# USB_Circuitry.net
KiCad netlist of a schematic drawn in Altium Designer
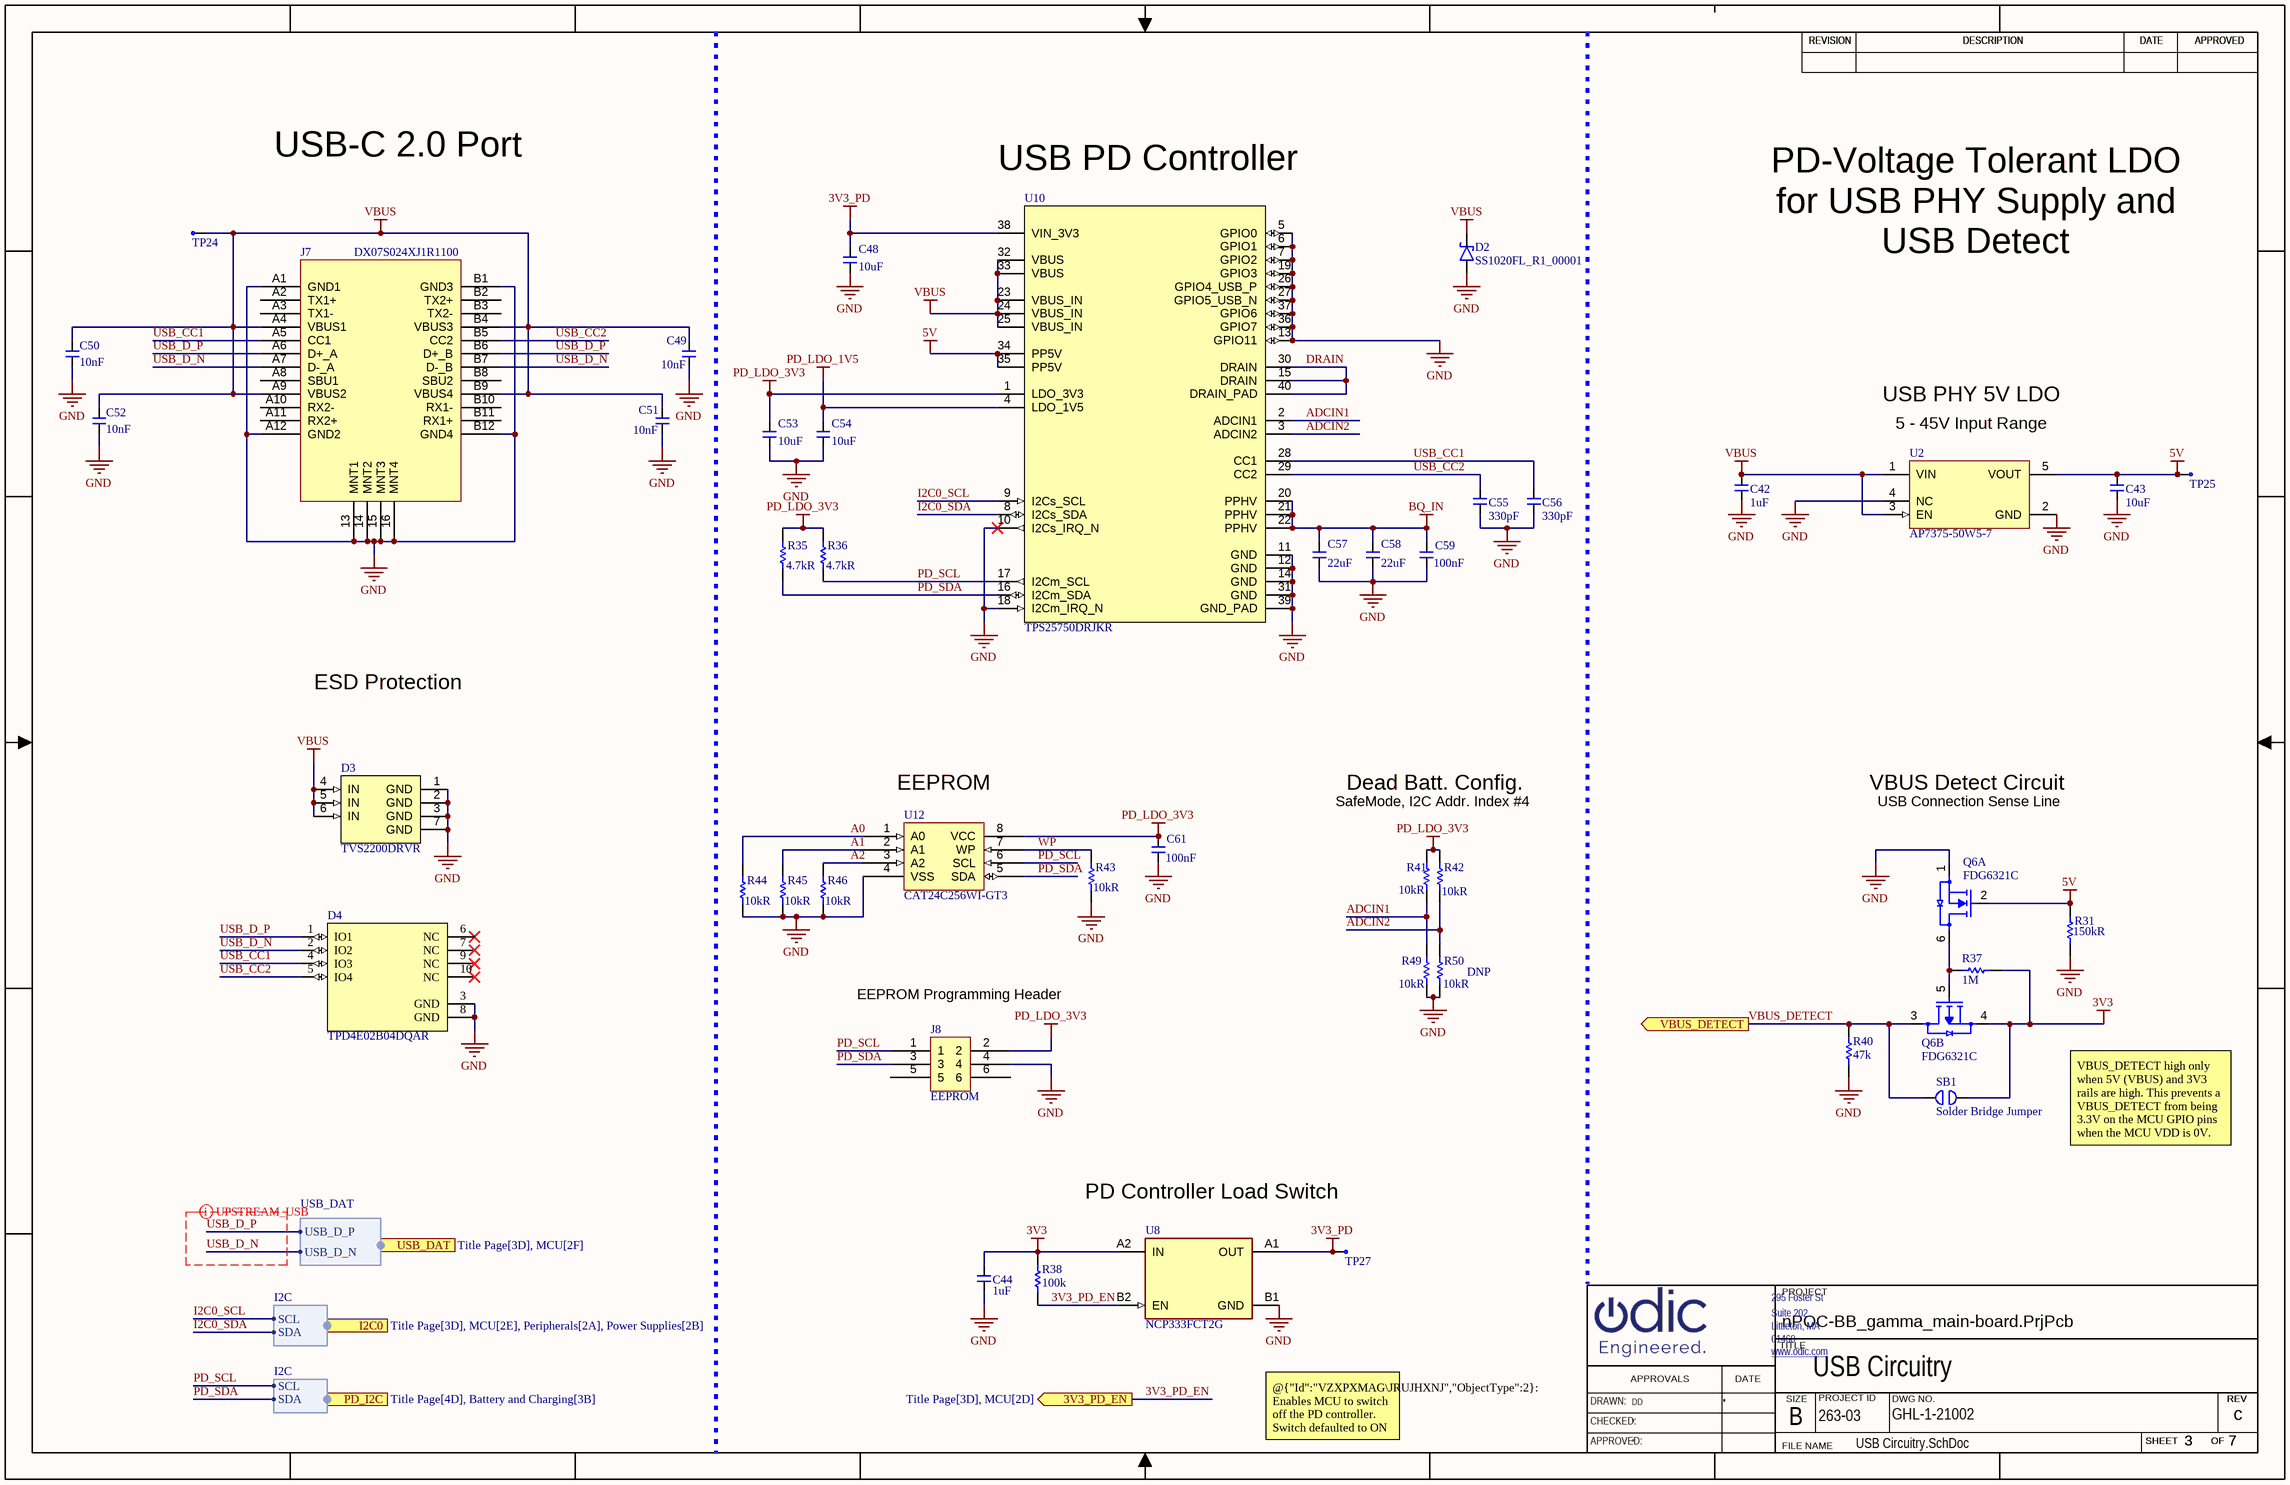
[diagram p0: USB Circuitry.SchDoc]

(export (version "E")
  (design (tool "Eeschema 10.0.6"))
  (components
    (comp (ref "C42")
      (value "1uF")
      (footprint "C0603")
      (description "Multilayer Ceramic Capacitors MLCC - SMD/SMT 1uF 50V 0603 RoHS")
      (fields (field (name "TOLERANCE") "10%"))
      (libsource (lib "Odic Inc") (part "cAP"))
    )
    (comp (ref "C43")
      (value "10uF")
      (footprint "C0402")
      (description "Ceramic capacitor SMD; 0402; 10uF; 10V; X5R; 20%")
      (fields (field (name "TOLERANCE") "20%"))
      (libsource (lib "Odic Inc") (part "cAP"))
    )
    (comp (ref "C44")
      (value "C0402_1u_6V3_10pct")
      (footprint "C0402")
      (description "Cap Ceramic 1uF 6.3V X5R 10% SMD 0402 85C Paper T/R")
      (fields (field (name "CAPACITANCE") "1uF") (field (name "TOLERANCE") "10%"))
      (libsource (lib "Odic Inc") (part "cAP"))
    )
    (comp (ref "C48")
      (value "C0402_10u_10V_20pct")
      (footprint "C0402")
      (description "Ceramic capacitor SMD; 0402; 10uF; 10V; X5R; 20%")
      (fields (field (name "CAPACITANCE") "10uF") (field (name "TOLERANCE") "20%"))
      (libsource (lib "Odic Inc") (part "cAP"))
    )
    (comp (ref "C49")
      (value "10nF")
      (footprint "C0402")
      (description "Multilayer Ceramic Capacitor, 0.01 uF, 35 V, ± 10%, X7R, 0402 [1005 Metric]")
      (fields (field (name "TOLERANCE") "10%") (field (name "Comment") "C0402_10n_35V_10pct"))
      (libsource (lib "Odic Inc") (part "cAP"))
    )
    (comp (ref "C50")
      (value "10nF")
      (footprint "C0402")
      (description "Multilayer Ceramic Capacitor, 0.01 uF, 35 V, ± 10%, X7R, 0402 [1005 Metric]")
      (fields (field (name "TOLERANCE") "10%") (field (name "Comment") "C0402_10n_35V_10pct"))
      (libsource (lib "Odic Inc") (part "cAP"))
    )
    (comp (ref "C51")
      (value "10nF")
      (footprint "C0402")
      (description "Multilayer Ceramic Capacitor, 0.01 uF, 35 V, ± 10%, X7R, 0402 [1005 Metric]")
      (fields (field (name "TOLERANCE") "10%") (field (name "Comment") "C0402_10n_35V_10pct"))
      (libsource (lib "Odic Inc") (part "cAP"))
    )
    (comp (ref "C52")
      (value "10nF")
      (footprint "C0402")
      (description "Multilayer Ceramic Capacitor, 0.01 uF, 35 V, ± 10%, X7R, 0402 [1005 Metric]")
      (fields (field (name "TOLERANCE") "10%") (field (name "Comment") "C0402_10n_35V_10pct"))
      (libsource (lib "Odic Inc") (part "cAP"))
    )
    (comp (ref "C53")
      (value "C0402_10u_10V_20pct")
      (footprint "C0402")
      (description "Ceramic capacitor SMD; 0402; 10uF; 10V; X5R; 20%")
      (fields (field (name "CAPACITANCE") "10uF") (field (name "TOLERANCE") "20%"))
      (libsource (lib "Odic Inc") (part "cAP"))
    )
    (comp (ref "C54")
      (value "C0402_10u_10V_20pct")
      (footprint "C0402")
      (description "Ceramic capacitor SMD; 0402; 10uF; 10V; X5R; 20%")
      (fields (field (name "CAPACITANCE") "10uF") (field (name "TOLERANCE") "20%"))
      (libsource (lib "Odic Inc") (part "cAP"))
    )
    (comp (ref "C55")
      (value "330pF")
      (footprint "C0402")
      (description "0402 330 pF 50 V ±5% Tolerance C0G SMT Multilayer Ceramic Capacitor")
      (fields (field (name "VOLTAGE") "50V") (field (name "TOLERANCE") "5%"))
      (libsource (lib "Odic Inc") (part "cAP"))
    )
    (comp (ref "C56")
      (value "330pF")
      (footprint "C0402")
      (description "0402 330 pF 50 V ±5% Tolerance C0G SMT Multilayer Ceramic Capacitor")
      (fields (field (name "VOLTAGE") "50V") (field (name "TOLERANCE") "5%"))
      (libsource (lib "Odic Inc") (part "cAP"))
    )
    (comp (ref "C57")
      (value "C0805_22u_25V_20pct")
      (footprint "c0805")
      (description "Multilayer Ceramic Capacitor, 22 uF, 25 V, ± 20%, X5R, 0805 [2012 Metric]")
      (fields (field (name "CAPACITANCE") "22uF"))
      (libsource (lib "Odic Inc") (part "cAP"))
    )
    (comp (ref "C58")
      (value "C0805_22u_25V_20pct")
      (footprint "c0805")
      (description "Multilayer Ceramic Capacitor, 22 uF, 25 V, ± 20%, X5R, 0805 [2012 Metric]")
      (fields (field (name "CAPACITANCE") "22uF"))
      (libsource (lib "Odic Inc") (part "cAP"))
    )
    (comp (ref "C59")
      (value "C0402_0u1_25V_10pct")
      (footprint "C0402")
      (description "Cap Ceramic 0.1uF 25V X5R 10% Pad SMD 0402 Multi Layer Ceramic Capacitor (MLCC)")
      (fields
        (field (name "VOLTAGE") "25V")
        (field (name "TOLERANCE") "10%")
        (field (name "CAPACITANCE") "100nF")
      )
      (libsource (lib "Odic Inc") (part "cAP"))
    )
    (comp (ref "C61")
      (value "C0402_0u1_25V_10pct")
      (footprint "C0402")
      (description "Cap Ceramic 0.1uF 25V X5R 10% Pad SMD 0402 Multi Layer Ceramic Capacitor (MLCC)")
      (fields
        (field (name "VOLTAGE") "25V")
        (field (name "TOLERANCE") "10%")
        (field (name "CAPACITANCE") "100nF")
      )
      (libsource (lib "Odic Inc") (part "cAP"))
    )
    (comp (ref "D2")
      (value "SS1020FL_R1_00001")
      (footprint "sod-123fl_AK")
      (description "Diode Schottky 20V 1A 2-Pin SOD-123FL T/R")
      (libsource (lib "Odic Inc") (part "Schottky"))
    )
    (comp (ref "D3")
      (value "TVS2200DRVR")
      (footprint "dfn7_2x2_p65mm")
      (description "22-V flat-clamp surge protection device 6-WSON -40 to 125")
      (libsource (lib "Odic Inc") (part "TVS2200DRVR-sym"))
    )
    (comp (ref "D4")
      (value "TPD4E02B04DQAR")
      (footprint "dfn10_1p1x2p6_p5mm")
      (description "Quad 0.25-pF, ±3.6-V, ±12-kV ESD protection diode for USB 3.0, HDMI 2.0 & High Speed Signals")
      (libsource (lib "Odic Inc") (part "TPD4E02B04DQAR-sym"))
    )
    (comp (ref "J7")
      (value "DX07S024XJ1R1100")
      (footprint "USB_JAE_DX07S024XJ1R1100")
      (libsource (lib "Odic Inc") (part "DX07S024XJ1R1100-symbol-1"))
    )
    (comp (ref "J8")
      (value "EEPROM")
      (footprint "tc2030-mcp-nl")
      (description "6 Pin Tag-Connect Header Footprint. Pads.")
      (libsource (lib "Odic Inc") (part "TC2030-FP-Symbol-1"))
    )
    (comp (ref "Q6")
      (value "FDG6321C")
      (footprint "SOT-363")
      (description "Trans Mosfet N/p-ch 25V 0.5A/0.41A 6-PIN SC-70 T/r")
      (libsource (lib "Odic Inc") (part "FGD6321C"))
    )
    (comp (ref "R31")
      (value "150kR")
      (footprint "R0402")
      (description "Res Thick Film 0402 150K Ohm 1% 0.063W ±100ppm/°C Molded SMD Paper T/R")
      (fields (field (name "TOLERANCE") "1%") (field (name "Comment") "R0402_150k_1pct"))
      (libsource (lib "Odic Inc") (part "RES"))
    )
    (comp (ref "R35")
      (value "R0402_4k7_1pct")
      (footprint "R0402")
      (description "RES 4.7K OHM 1% 1/16W 0402")
      (fields (field (name "TOLERANCE") "1%") (field (name "RESISTANCE") "4.7kR"))
      (libsource (lib "Odic Inc") (part "RES"))
    )
    (comp (ref "R36")
      (value "R0402_4k7_1pct")
      (footprint "R0402")
      (description "RES 4.7K OHM 1% 1/16W 0402")
      (fields (field (name "TOLERANCE") "1%") (field (name "RESISTANCE") "4.7kR"))
      (libsource (lib "Odic Inc") (part "RES"))
    )
    (comp (ref "R37")
      (value "1M")
      (footprint "R0402")
      (description "Res Thick Film 0402 1M Ohm 1% 0.063W(1/16W) ±100ppm/C Pad SMD T/R")
      (fields (field (name "TOLERANCE") "1%"))
      (libsource (lib "Odic Inc") (part "RES"))
    )
    (comp (ref "R38")
      (value "100k")
      (footprint "R0402")
      (description "Res General Purpose Thick Film 0402 100K Ohm 1% 1/16W ±100ppm/°C Molded SMD Paper T/R")
      (fields (field (name "TOLERANCE") "1%"))
      (libsource (lib "Odic Inc") (part "RES"))
    )
    (comp (ref "R40")
      (value "47k")
      (footprint "R0402")
      (description "Res General Purpose Thick Film 0402 47K Ohm 1% 1/16W ±100ppm/°C Molded SMD Paper T/R")
      (fields (field (name "TOLERANCE") "1%"))
      (libsource (lib "Odic Inc") (part "RES"))
    )
    (comp (ref "R41")
      (value "R0402_10k_1pct")
      (footprint "R0402")
      (description "Res Thick Film 0402 10K Ohm 1% 1/16W ±100ppm/°C Molded SMD SMD T/R")
      (fields (field (name "RESISTANCE") "10kR") (field (name "TOLERANCE") "1%"))
      (libsource (lib "Odic Inc") (part "RES"))
    )
    (comp (ref "R42")
      (value "R0402_10k_1pct")
      (footprint "R0402")
      (description "Res Thick Film 0402 10K Ohm 1% 1/16W ±100ppm/°C Molded SMD SMD T/R")
      (fields (field (name "RESISTANCE") "10kR") (field (name "TOLERANCE") "1%"))
      (libsource (lib "Odic Inc") (part "RES"))
    )
    (comp (ref "R43")
      (value "R0402_10k_1pct")
      (footprint "R0402")
      (description "Res Thick Film 0402 10K Ohm 1% 1/16W ±100ppm/°C Molded SMD SMD T/R")
      (fields (field (name "RESISTANCE") "10kR") (field (name "TOLERANCE") "1%"))
      (libsource (lib "Odic Inc") (part "RES"))
    )
    (comp (ref "R44")
      (value "R0402_10k_1pct")
      (footprint "R0402")
      (description "Res Thick Film 0402 10K Ohm 1% 1/16W ±100ppm/°C Molded SMD SMD T/R")
      (fields (field (name "RESISTANCE") "10kR") (field (name "TOLERANCE") "1%"))
      (libsource (lib "Odic Inc") (part "RES"))
    )
    (comp (ref "R45")
      (value "R0402_10k_1pct")
      (footprint "R0402")
      (description "Res Thick Film 0402 10K Ohm 1% 1/16W ±100ppm/°C Molded SMD SMD T/R")
      (fields (field (name "RESISTANCE") "10kR") (field (name "TOLERANCE") "1%"))
      (libsource (lib "Odic Inc") (part "RES"))
    )
    (comp (ref "R46")
      (value "R0402_10k_1pct")
      (footprint "R0402")
      (description "Res Thick Film 0402 10K Ohm 1% 1/16W ±100ppm/°C Molded SMD SMD T/R")
      (fields (field (name "RESISTANCE") "10kR") (field (name "TOLERANCE") "1%"))
      (libsource (lib "Odic Inc") (part "RES"))
    )
    (comp (ref "R49")
      (value "R0402_10k_1pct")
      (footprint "R0402")
      (description "Res Thick Film 0402 10K Ohm 1% 1/16W ±100ppm/°C Molded SMD SMD T/R")
      (fields (field (name "RESISTANCE") "10kR") (field (name "TOLERANCE") "1%"))
      (libsource (lib "Odic Inc") (part "RES"))
    )
    (comp (ref "R50")
      (value "R0402_10k_1pct")
      (footprint "R0402")
      (description "Res Thick Film 0402 10K Ohm 1% 1/16W ±100ppm/°C Molded SMD SMD T/R")
      (fields
        (field (name "RESISTANCE") "10kR")
        (field (name "TOLERANCE") "1%")
        (field (name "INSTALL") "DNP")
      )
      (libsource (lib "Odic Inc") (part "RES"))
    )
    (comp (ref "SB1")
      (value "Solder Bridge Jumper")
      (footprint "Solder-Bridge")
      (description "0 Ohm solder bridge jumper")
      (libsource (lib "Odic Inc") (part "Solder Bridge Jumper"))
    )
    (comp (ref "TP24")
      (value "TPC30")
      (footprint "tpc30")
      (description "Test Point Circle 30")
      (libsource (lib "Odic Inc") (part "TPC"))
    )
    (comp (ref "TP25")
      (value "TPC30")
      (footprint "tpc30")
      (description "Test Point Circle 30")
      (libsource (lib "Odic Inc") (part "TPC"))
    )
    (comp (ref "TP27")
      (value "TPC30")
      (footprint "tpc30")
      (description "Test Point Circle 30")
      (libsource (lib "Odic Inc") (part "TPC"))
    )
    (comp (ref "U2")
      (value "AP7375-50W5-7")
      (footprint "SOT25")
      (description "Fixed 5V LDO Voltage Regulators LDO CMOS LowCurr SOT25 TR 3K")
      (libsource (lib "Odic Inc") (part "0611416dd6b6fc2280b1ddb1fddec67"))
    )
    (comp (ref "U8")
      (value "NCP333FCT2G")
      (footprint "bga4_p743xp743_p4mm")
      (description "IC LOAD SWITCH W/DIS 1.5A 4WLCSP")
      (libsource (lib "Odic Inc") (part "97019fd276bc7644be76e1f711e9589"))
    )
    (comp (ref "U10")
      (value "TPS25750DRJKR")
      (footprint "qfn40_6x4_p4mm-RJK0038B")
      (description "Highly integrated USB Type-C® and USB PD controller with pre-configured GUI 38-WQFN -40 to 125")
      (libsource (lib "Odic Inc") (part "TPS25750DRJKR-Symbol-1"))
    )
    (comp (ref "U12")
      (value "CAT24C256WI-GT3")
      (footprint "SO8")
      (description "IC EEPROM 256KBIT 400KHZ 8SOIC")
      (libsource (lib "Odic Inc") (part "CAT24C256WI-GT3-Symbol-1"))
    )
  )
  (nets
    (net (code "3") (name "/3V3_PD_EN") (class "Default")
      (node (ref "R38") (pin "1") (pinfunction "1_1") (pintype "passive"))
      (node (ref "U8") (pin "B2") (pinfunction "EN_B2") (pintype "input"))
    )
    (net (code "4") (name "/A0") (class "Default")
      (node (ref "R44") (pin "2") (pinfunction "2_2") (pintype "passive"))
      (node (ref "U12") (pin "1") (pinfunction "A0_1") (pintype "input"))
    )
    (net (code "5") (name "/A1") (class "Default")
      (node (ref "R45") (pin "2") (pinfunction "2_2") (pintype "passive"))
      (node (ref "U12") (pin "2") (pinfunction "A1_2") (pintype "input"))
    )
    (net (code "6") (name "/A2") (class "Default")
      (node (ref "R46") (pin "2") (pinfunction "2_2") (pintype "passive"))
      (node (ref "U12") (pin "3") (pinfunction "A2_3") (pintype "input"))
    )
    (net (code "7") (name "/ADCIN1") (class "Default")
      (node (ref "R41") (pin "1") (pinfunction "1_1") (pintype "passive"))
      (node (ref "R49") (pin "2") (pinfunction "2_2") (pintype "passive"))
      (node (ref "U10") (pin "2") (pinfunction "ADCIN1_2") (pintype "passive"))
    )
    (net (code "8") (name "/ADCIN2") (class "Default")
      (node (ref "R42") (pin "1") (pinfunction "1_1") (pintype "passive"))
      (node (ref "R50") (pin "2") (pinfunction "2_2") (pintype "passive"))
      (node (ref "U10") (pin "3") (pinfunction "ADCIN2_3") (pintype "passive"))
    )
    (net (code "9") (name "/DRAIN") (class "Default")
      (node (ref "U10") (pin "15") (pinfunction "DRAIN_15") (pintype "passive"))
      (node (ref "U10") (pin "30") (pinfunction "DRAIN_30") (pintype "passive"))
      (node (ref "U10") (pin "40") (pinfunction "DRAIN_PAD_40") (pintype "passive"))
    )
    (net (code "10") (name "/I2C0_SCL") (class "Default")
      (node (ref "U10") (pin "9") (pinfunction "I2Cs_SCL_9") (pintype "input"))
    )
    (net (code "11") (name "/I2C0_SDA") (class "Default")
      (node (ref "U10") (pin "8") (pinfunction "I2Cs_SDA_8") (pintype "bidirectional"))
    )
    (net (code "12") (name "/PD_SCL") (class "Default")
      (node (ref "J8") (pin "1") (pinfunction "1_1") (pintype "passive"))
      (node (ref "R36") (pin "1") (pinfunction "1_1") (pintype "passive"))
      (node (ref "U10") (pin "17") (pinfunction "I2Cm_SCL_17") (pintype "output"))
      (node (ref "U12") (pin "6") (pinfunction "SCL_6") (pintype "input"))
    )
    (net (code "13") (name "/PD_SDA") (class "Default")
      (node (ref "J8") (pin "3") (pinfunction "3_3") (pintype "passive"))
      (node (ref "R35") (pin "1") (pinfunction "1_1") (pintype "passive"))
      (node (ref "U10") (pin "16") (pinfunction "I2Cm_SDA_16") (pintype "bidirectional"))
      (node (ref "U12") (pin "5") (pinfunction "SDA_5") (pintype "bidirectional"))
    )
    (net (code "14") (name "/USB_CC1") (class "Default")
      (node (ref "C56") (pin "2") (pinfunction "2_2") (pintype "passive"))
      (node (ref "D4") (pin "4") (pinfunction "IO3_4") (pintype "bidirectional"))
      (node (ref "J7") (pin "A5") (pinfunction "CC1_A5") (pintype "passive"))
      (node (ref "U10") (pin "28") (pinfunction "CC1_28") (pintype "passive"))
    )
    (net (code "15") (name "/USB_CC2") (class "Default")
      (node (ref "C55") (pin "2") (pinfunction "2_2") (pintype "passive"))
      (node (ref "D4") (pin "5") (pinfunction "IO4_5") (pintype "bidirectional"))
      (node (ref "J7") (pin "B5") (pinfunction "CC2_B5") (pintype "passive"))
      (node (ref "U10") (pin "29") (pinfunction "CC2_29") (pintype "passive"))
    )
    (net (code "16") (name "/USB_D_N") (class "Default")
      (node (ref "D4") (pin "2") (pinfunction "IO2_2") (pintype "bidirectional"))
      (node (ref "J7") (pin "A7") (pinfunction "D-_A_A7") (pintype "passive"))
      (node (ref "J7") (pin "B7") (pinfunction "D-_B_B7") (pintype "passive"))
    )
    (net (code "17") (name "/USB_D_P") (class "Default")
      (node (ref "D4") (pin "1") (pinfunction "IO1_1") (pintype "bidirectional"))
      (node (ref "J7") (pin "A6") (pinfunction "D+_A_A6") (pintype "passive"))
      (node (ref "J7") (pin "B6") (pinfunction "D+_B_B6") (pintype "passive"))
    )
    (net (code "18") (name "/VBUS_DETECT") (class "Default")
      (node (ref "Q6") (pin "3") (pinfunction "D2_3") (pintype "passive"))
      (node (ref "R40") (pin "2") (pinfunction "2_2") (pintype "passive"))
      (node (ref "SB1") (pin "1") (pinfunction "1_1") (pintype "passive"))
    )
    (net (code "19") (name "/WP") (class "Default")
      (node (ref "R43") (pin "2") (pinfunction "2_2") (pintype "passive"))
      (node (ref "U12") (pin "7") (pinfunction "WP_7") (pintype "input"))
    )
    (net (code "22") (name "3V3") (class "Default")
      (node (ref "C44") (pin "2") (pinfunction "2_2") (pintype "passive"))
      (node (ref "Q6") (pin "4") (pinfunction "S2_4") (pintype "passive"))
      (node (ref "R37") (pin "2") (pinfunction "2_2") (pintype "passive"))
      (node (ref "R38") (pin "2") (pinfunction "2_2") (pintype "passive"))
      (node (ref "SB1") (pin "2") (pinfunction "2_2") (pintype "passive"))
      (node (ref "U8") (pin "A2") (pinfunction "IN_A2") (pintype "power_in"))
    )
    (net (code "23") (name "3V3_PD") (class "Default")
      (node (ref "C48") (pin "2") (pinfunction "2_2") (pintype "passive"))
      (node (ref "TP27") (pin "1") (pinfunction "1_1") (pintype "passive"))
      (node (ref "U10") (pin "38") (pinfunction "VIN_3V3_38") (pintype "power_in"))
      (node (ref "U8") (pin "A1") (pinfunction "OUT_A1") (pintype "power_in"))
    )
    (net (code "24") (name "5V") (class "Default")
      (node (ref "C43") (pin "2") (pinfunction "2_2") (pintype "passive"))
      (node (ref "Q6") (pin "2") (pinfunction "G1_2") (pintype "passive"))
      (node (ref "R31") (pin "2") (pinfunction "2_2") (pintype "passive"))
      (node (ref "TP25") (pin "1") (pinfunction "1_1") (pintype "passive"))
      (node (ref "U10") (pin "34") (pinfunction "PP5V_34") (pintype "power_in"))
      (node (ref "U10") (pin "35") (pinfunction "PP5V_35") (pintype "power_in"))
      (node (ref "U2") (pin "5") (pinfunction "VOUT_5") (pintype "power_in"))
    )
    (net (code "25") (name "BQ_IN") (class "Default")
      (node (ref "C57") (pin "2") (pinfunction "2_2") (pintype "passive"))
      (node (ref "C58") (pin "2") (pinfunction "2_2") (pintype "passive"))
      (node (ref "C59") (pin "2") (pinfunction "2_2") (pintype "passive"))
      (node (ref "U10") (pin "20") (pinfunction "PPHV_20") (pintype "passive"))
      (node (ref "U10") (pin "21") (pinfunction "PPHV_21") (pintype "passive"))
      (node (ref "U10") (pin "22") (pinfunction "PPHV_22") (pintype "passive"))
    )
    (net (code "26") (name "GND") (class "Default")
      (node (ref "C42") (pin "1") (pinfunction "1_1") (pintype "passive"))
      (node (ref "C43") (pin "1") (pinfunction "1_1") (pintype "passive"))
      (node (ref "C44") (pin "1") (pinfunction "1_1") (pintype "passive"))
      (node (ref "C48") (pin "1") (pinfunction "1_1") (pintype "passive"))
      (node (ref "C49") (pin "1") (pinfunction "1_1") (pintype "passive"))
      (node (ref "C50") (pin "1") (pinfunction "1_1") (pintype "passive"))
      (node (ref "C51") (pin "1") (pinfunction "1_1") (pintype "passive"))
      (node (ref "C52") (pin "1") (pinfunction "1_1") (pintype "passive"))
      (node (ref "C53") (pin "1") (pinfunction "1_1") (pintype "passive"))
      (node (ref "C54") (pin "1") (pinfunction "1_1") (pintype "passive"))
      (node (ref "C55") (pin "1") (pinfunction "1_1") (pintype "passive"))
      (node (ref "C56") (pin "1") (pinfunction "1_1") (pintype "passive"))
      (node (ref "C57") (pin "1") (pinfunction "1_1") (pintype "passive"))
      (node (ref "C58") (pin "1") (pinfunction "1_1") (pintype "passive"))
      (node (ref "C59") (pin "1") (pinfunction "1_1") (pintype "passive"))
      (node (ref "C61") (pin "1") (pinfunction "1_1") (pintype "passive"))
      (node (ref "D2") (pin "A") (pinfunction "A_A") (pintype "passive"))
      (node (ref "D3") (pin "1") (pinfunction "GND_1") (pintype "power_in"))
      (node (ref "D3") (pin "2") (pinfunction "GND_2") (pintype "power_in"))
      (node (ref "D3") (pin "3") (pinfunction "GND_3") (pintype "power_in"))
      (node (ref "D3") (pin "7") (pinfunction "GND_7") (pintype "power_in"))
      (node (ref "D4") (pin "3") (pinfunction "GND_3") (pintype "power_in"))
      (node (ref "D4") (pin "8") (pinfunction "GND_8") (pintype "power_in"))
      (node (ref "J7") (pin "13") (pinfunction "MNT1_13") (pintype "passive"))
      (node (ref "J7") (pin "14") (pinfunction "MNT2_14") (pintype "passive"))
      (node (ref "J7") (pin "15") (pinfunction "MNT3_15") (pintype "passive"))
      (node (ref "J7") (pin "16") (pinfunction "MNT4_16") (pintype "passive"))
      (node (ref "J7") (pin "A1") (pinfunction "GND1_A1") (pintype "passive"))
      (node (ref "J7") (pin "A12") (pinfunction "GND2_A12") (pintype "passive"))
      (node (ref "J7") (pin "B1") (pinfunction "GND3_B1") (pintype "passive"))
      (node (ref "J7") (pin "B12") (pinfunction "GND4_B12") (pintype "passive"))
      (node (ref "J8") (pin "4") (pinfunction "4_4") (pintype "passive"))
      (node (ref "Q6") (pin "1") (pinfunction "S1_1") (pintype "passive"))
      (node (ref "R31") (pin "1") (pinfunction "1_1") (pintype "passive"))
      (node (ref "R40") (pin "1") (pinfunction "1_1") (pintype "passive"))
      (node (ref "R43") (pin "1") (pinfunction "1_1") (pintype "passive"))
      (node (ref "R44") (pin "1") (pinfunction "1_1") (pintype "passive"))
      (node (ref "R45") (pin "1") (pinfunction "1_1") (pintype "passive"))
      (node (ref "R46") (pin "1") (pinfunction "1_1") (pintype "passive"))
      (node (ref "R49") (pin "1") (pinfunction "1_1") (pintype "passive"))
      (node (ref "R50") (pin "1") (pinfunction "1_1") (pintype "passive"))
      (node (ref "U10") (pin "10") (pinfunction "I2Cs_IRQ_N_10") (pintype "output"))
      (node (ref "U10") (pin "11") (pinfunction "GND_11") (pintype "power_in"))
      (node (ref "U10") (pin "12") (pinfunction "GND_12") (pintype "power_in"))
      (node (ref "U10") (pin "13") (pinfunction "GPIO11_13") (pintype "bidirectional"))
      (node (ref "U10") (pin "14") (pinfunction "GND_14") (pintype "power_in"))
      (node (ref "U10") (pin "18") (pinfunction "I2Cm_IRQ_N_18") (pintype "input"))
      (node (ref "U10") (pin "19") (pinfunction "GPIO3_19") (pintype "bidirectional"))
      (node (ref "U10") (pin "26") (pinfunction "GPIO4_USB_P_26") (pintype "bidirectional"))
      (node (ref "U10") (pin "27") (pinfunction "GPIO5_USB_N_27") (pintype "bidirectional"))
      (node (ref "U10") (pin "31") (pinfunction "GND_31") (pintype "power_in"))
      (node (ref "U10") (pin "36") (pinfunction "GPIO7_36") (pintype "bidirectional"))
      (node (ref "U10") (pin "37") (pinfunction "GPIO6_37") (pintype "bidirectional"))
      (node (ref "U10") (pin "39") (pinfunction "GND_PAD_39") (pintype "power_in"))
      (node (ref "U10") (pin "5") (pinfunction "GPIO0_5") (pintype "bidirectional"))
      (node (ref "U10") (pin "6") (pinfunction "GPIO1_6") (pintype "bidirectional"))
      (node (ref "U10") (pin "7") (pinfunction "GPIO2_7") (pintype "bidirectional"))
      (node (ref "U12") (pin "4") (pinfunction "VSS_4") (pintype "passive"))
      (node (ref "U2") (pin "2") (pinfunction "GND_2") (pintype "power_in"))
      (node (ref "U2") (pin "4") (pinfunction "NC_4") (pintype "passive"))
      (node (ref "U8") (pin "B1") (pinfunction "GND_B1") (pintype "power_in"))
    )
    (net (code "27") (name "Net-(Q6A-D1)") (class "Default")
      (node (ref "Q6") (pin "5") (pinfunction "G2_5") (pintype "passive"))
      (node (ref "Q6") (pin "6") (pinfunction "D1_6") (pintype "passive"))
      (node (ref "R37") (pin "1") (pinfunction "1_1") (pintype "passive"))
    )
    (net (code "28") (name "PD_LDO_1V5") (class "Default")
      (node (ref "C54") (pin "2") (pinfunction "2_2") (pintype "passive"))
      (node (ref "U10") (pin "4") (pinfunction "LDO_1V5_4") (pintype "passive"))
    )
    (net (code "29") (name "PD_LDO_3V3") (class "Default")
      (node (ref "C53") (pin "2") (pinfunction "2_2") (pintype "passive"))
      (node (ref "C61") (pin "2") (pinfunction "2_2") (pintype "passive"))
      (node (ref "J8") (pin "2") (pinfunction "2_2") (pintype "passive"))
      (node (ref "R35") (pin "2") (pinfunction "2_2") (pintype "passive"))
      (node (ref "R36") (pin "2") (pinfunction "2_2") (pintype "passive"))
      (node (ref "R41") (pin "2") (pinfunction "2_2") (pintype "passive"))
      (node (ref "R42") (pin "2") (pinfunction "2_2") (pintype "passive"))
      (node (ref "U10") (pin "1") (pinfunction "LDO_3V3_1") (pintype "passive"))
      (node (ref "U12") (pin "8") (pinfunction "VCC_8") (pintype "passive"))
    )
    (net (code "30") (name "VBUS") (class "Default")
      (node (ref "C42") (pin "2") (pinfunction "2_2") (pintype "passive"))
      (node (ref "C49") (pin "2") (pinfunction "2_2") (pintype "passive"))
      (node (ref "C50") (pin "2") (pinfunction "2_2") (pintype "passive"))
      (node (ref "C51") (pin "2") (pinfunction "2_2") (pintype "passive"))
      (node (ref "C52") (pin "2") (pinfunction "2_2") (pintype "passive"))
      (node (ref "D2") (pin "K") (pinfunction "K_K") (pintype "passive"))
      (node (ref "D3") (pin "4") (pinfunction "IN_4") (pintype "input"))
      (node (ref "D3") (pin "5") (pinfunction "IN_5") (pintype "input"))
      (node (ref "D3") (pin "6") (pinfunction "IN_6") (pintype "input"))
      (node (ref "J7") (pin "A4") (pinfunction "VBUS1_A4") (pintype "passive"))
      (node (ref "J7") (pin "A9") (pinfunction "VBUS2_A9") (pintype "passive"))
      (node (ref "J7") (pin "B4") (pinfunction "VBUS3_B4") (pintype "passive"))
      (node (ref "J7") (pin "B9") (pinfunction "VBUS4_B9") (pintype "passive"))
      (node (ref "TP24") (pin "1") (pinfunction "1_1") (pintype "passive"))
      (node (ref "U10") (pin "23") (pinfunction "VBUS_IN_23") (pintype "power_in"))
      (node (ref "U10") (pin "24") (pinfunction "VBUS_IN_24") (pintype "power_in"))
      (node (ref "U10") (pin "25") (pinfunction "VBUS_IN_25") (pintype "power_in"))
      (node (ref "U10") (pin "32") (pinfunction "VBUS_32") (pintype "power_in"))
      (node (ref "U10") (pin "33") (pinfunction "VBUS_33") (pintype "power_in"))
      (node (ref "U2") (pin "1") (pinfunction "VIN_1") (pintype "power_in"))
      (node (ref "U2") (pin "3") (pinfunction "EN_3") (pintype "input"))
    )
    (net (code "31") (name "unconnected-(D4-NC-Pad6)") (class "Default")
      (node (ref "D4") (pin "6") (pinfunction "NC_6") (pintype "passive+no_connect"))
    )
    (net (code "32") (name "unconnected-(D4-NC-Pad7)") (class "Default")
      (node (ref "D4") (pin "7") (pinfunction "NC_7") (pintype "passive+no_connect"))
    )
    (net (code "33") (name "unconnected-(D4-NC-Pad9)") (class "Default")
      (node (ref "D4") (pin "9") (pinfunction "NC_9") (pintype "passive+no_connect"))
    )
    (net (code "34") (name "unconnected-(D4-NC-Pad10)") (class "Default")
      (node (ref "D4") (pin "10") (pinfunction "NC_10") (pintype "passive+no_connect"))
    )
    (net (code "35") (name "unconnected-(J7-RX1+-PadB11)") (class "Default")
      (node (ref "J7") (pin "B11") (pinfunction "RX1+_B11") (pintype "passive"))
    )
    (net (code "36") (name "unconnected-(J7-RX1--PadB10)") (class "Default")
      (node (ref "J7") (pin "B10") (pinfunction "RX1-_B10") (pintype "passive"))
    )
    (net (code "37") (name "unconnected-(J7-RX2+-PadA11)") (class "Default")
      (node (ref "J7") (pin "A11") (pinfunction "RX2+_A11") (pintype "passive"))
    )
    (net (code "38") (name "unconnected-(J7-RX2--PadA10)") (class "Default")
      (node (ref "J7") (pin "A10") (pinfunction "RX2-_A10") (pintype "passive"))
    )
    (net (code "39") (name "unconnected-(J7-SBU1-PadA8)") (class "Default")
      (node (ref "J7") (pin "A8") (pinfunction "SBU1_A8") (pintype "passive"))
    )
    (net (code "40") (name "unconnected-(J7-SBU2-PadB8)") (class "Default")
      (node (ref "J7") (pin "B8") (pinfunction "SBU2_B8") (pintype "passive"))
    )
    (net (code "41") (name "unconnected-(J7-TX1+-PadA2)") (class "Default")
      (node (ref "J7") (pin "A2") (pinfunction "TX1+_A2") (pintype "passive"))
    )
    (net (code "42") (name "unconnected-(J7-TX1--PadA3)") (class "Default")
      (node (ref "J7") (pin "A3") (pinfunction "TX1-_A3") (pintype "passive"))
    )
    (net (code "43") (name "unconnected-(J7-TX2+-PadB2)") (class "Default")
      (node (ref "J7") (pin "B2") (pinfunction "TX2+_B2") (pintype "passive"))
    )
    (net (code "44") (name "unconnected-(J7-TX2--PadB3)") (class "Default")
      (node (ref "J7") (pin "B3") (pinfunction "TX2-_B3") (pintype "passive"))
    )
    (net (code "45") (name "unconnected-(J8-Pad5)") (class "Default")
      (node (ref "J8") (pin "5") (pinfunction "5_5") (pintype "passive"))
    )
    (net (code "46") (name "unconnected-(J8-Pad6)") (class "Default")
      (node (ref "J8") (pin "6") (pinfunction "6_6") (pintype "passive"))
    )
  )
)
